# SAS_rev04.net
KiCad netlist of a schematic drawn in EAGLE
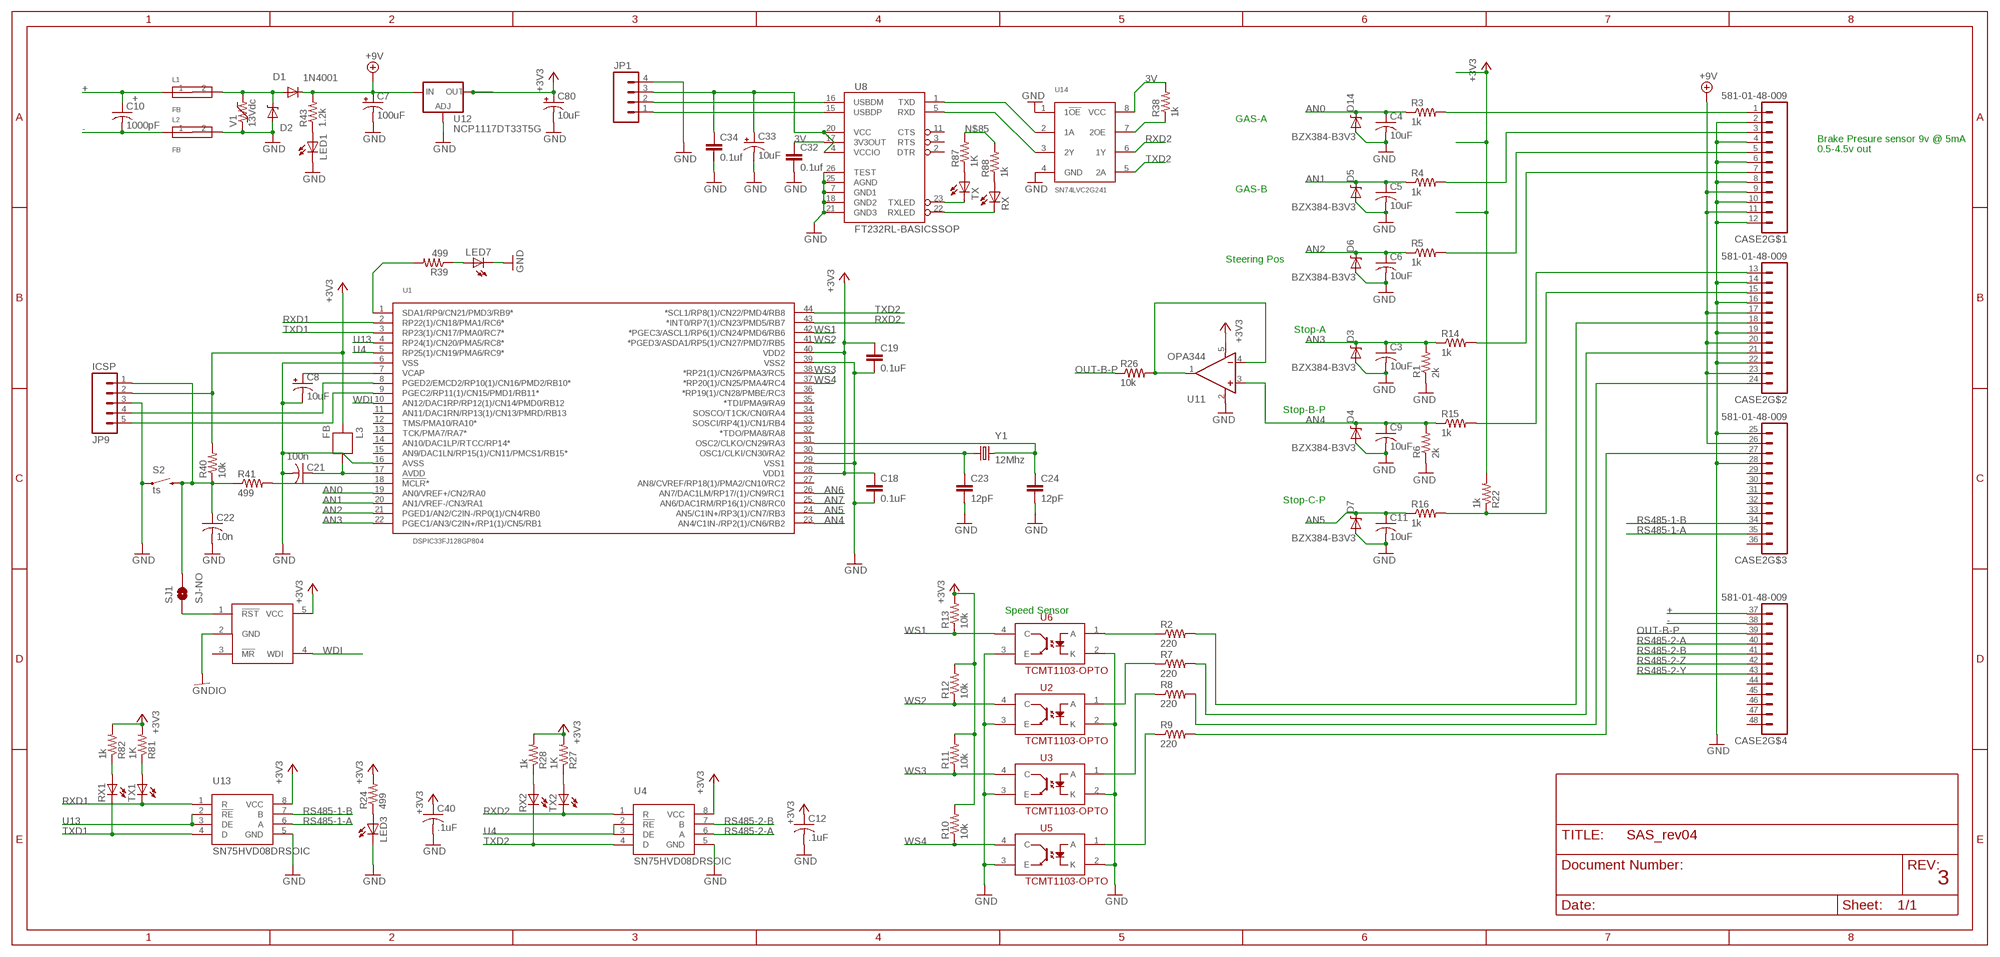
[diagram p0: schematic, sheet 1]

(export (version "E")
  (design (tool "Eeschema 10.0.6"))
  (components
    (comp (ref "C3")
      (value "10uF")
      (footprint "eagle-import:C0805")
      (libsource (lib "eagle-import") (part "C-USC0805"))
    )
    (comp (ref "C4")
      (value "10uF")
      (footprint "eagle-import:C0805")
      (libsource (lib "eagle-import") (part "C-USC0805"))
    )
    (comp (ref "C5")
      (value "10uF")
      (footprint "eagle-import:C0805")
      (libsource (lib "eagle-import") (part "C-USC0805"))
    )
    (comp (ref "C6")
      (value "10uF")
      (footprint "eagle-import:C0805")
      (libsource (lib "eagle-import") (part "C-USC0805"))
    )
    (comp (ref "C7")
      (value "100uF")
      (footprint "eagle-import:EIA7343")
      (libsource (lib "eagle-import") (part "SparkFun-Capacitors_CAP_POL7343"))
    )
    (comp (ref "C8")
      (value "10uF")
      (footprint "eagle-import:EIA3216-16V")
      (fields (field (name "PARTNO") "T491A106M016AT"))
      (libsource (lib "eagle-import") (part "CAP-POL_10UF_16V"))
    )
    (comp (ref "C9")
      (value "10uF")
      (footprint "eagle-import:C0805")
      (libsource (lib "eagle-import") (part "C-USC0805"))
    )
    (comp (ref "C10")
      (value "1000pF")
      (footprint "eagle-import:C1825")
      (libsource (lib "eagle-import") (part "C-USC1825"))
    )
    (comp (ref "C11")
      (value "10uF")
      (footprint "eagle-import:C0805")
      (libsource (lib "eagle-import") (part "C-USC0805"))
    )
    (comp (ref "C12")
      (value ".1uF")
      (footprint "eagle-import:0603")
      (fields (field (name "PARTNO") "CC0603ZRY5V9BB104"))
      (libsource (lib "eagle-import") (part "CAP_0.1UF_50V"))
    )
    (comp (ref "C18")
      (value "0.1uF")
      (footprint "eagle-import:0805")
      (libsource (lib "eagle-import") (part "SparkFun-Capacitors_CAP0805"))
    )
    (comp (ref "C19")
      (value "0.1uF")
      (footprint "eagle-import:0805")
      (libsource (lib "eagle-import") (part "SparkFun-Capacitors_CAP0805"))
    )
    (comp (ref "C21")
      (value "100n")
      (footprint "eagle-import:C0805")
      (libsource (lib "eagle-import") (part "C-USC0805"))
    )
    (comp (ref "C22")
      (value "10n")
      (footprint "eagle-import:0603")
      (fields (field (name "PARTNO") "CL10F103ZB8NNNC"))
      (libsource (lib "eagle-import") (part "CAP_10NF_50V"))
    )
    (comp (ref "C23")
      (value "12pF")
      (footprint "eagle-import:0805")
      (libsource (lib "eagle-import") (part "SparkFun-Capacitors_CAP0805"))
    )
    (comp (ref "C24")
      (value "12pF")
      (footprint "eagle-import:0805")
      (libsource (lib "eagle-import") (part "SparkFun-Capacitors_CAP0805"))
    )
    (comp (ref "C32")
      (value "0.1uf")
      (footprint "eagle-import:0805")
      (libsource (lib "eagle-import") (part "CAP0805"))
    )
    (comp (ref "C33")
      (value "10uF")
      (footprint "eagle-import:EIA3216")
      (libsource (lib "eagle-import") (part "CAP_POL1206"))
    )
    (comp (ref "C34")
      (value "0.1uf")
      (footprint "eagle-import:0805")
      (libsource (lib "eagle-import") (part "CAP0805"))
    )
    (comp (ref "C40")
      (value ".1uF")
      (footprint "eagle-import:0603")
      (fields (field (name "PARTNO") "CC0603ZRY5V9BB104"))
      (libsource (lib "eagle-import") (part "CAP_0.1UF_50V"))
    )
    (comp (ref "C80")
      (value "10uF")
      (footprint "eagle-import:POLC1206")
      (libsource (lib "eagle-import") (part "POLCAP"))
    )
    (comp (ref "CASE2")
      (value "581-01-48-009")
      (footprint "eagle-import:581-01-48-009")
      (libsource (lib "eagle-import") (part "581-01-48-009"))
    )
    (comp (ref "D1")
      (value "1N4001")
      (footprint "eagle-import:SOD123")
      (libsource (lib "eagle-import") (part "DIODE-SOD123"))
    )
    (comp (ref "D2")
      (value "MM5Z30")
      (footprint "eagle-import:SOD-523F")
      (libsource (lib "eagle-import") (part "MM5Z30"))
    )
    (comp (ref "D3")
      (value "BZX384-B3V3")
      (footprint "eagle-import:SOD-323")
      (libsource (lib "eagle-import") (part "DIODE-ZENER-BZT52"))
    )
    (comp (ref "D4")
      (value "BZX384-B3V3")
      (footprint "eagle-import:SOD-323")
      (libsource (lib "eagle-import") (part "DIODE-ZENER-BZT52"))
    )
    (comp (ref "D5")
      (value "BZX384-B3V3")
      (footprint "eagle-import:SOD-323")
      (libsource (lib "eagle-import") (part "DIODE-ZENER-BZT52"))
    )
    (comp (ref "D6")
      (value "BZX384-B3V3")
      (footprint "eagle-import:SOD-323")
      (libsource (lib "eagle-import") (part "DIODE-ZENER-BZT52"))
    )
    (comp (ref "D7")
      (value "BZX384-B3V3")
      (footprint "eagle-import:SOD-323")
      (libsource (lib "eagle-import") (part "DIODE-ZENER-BZT52"))
    )
    (comp (ref "D14")
      (value "BZX384-B3V3")
      (footprint "eagle-import:SOD-323")
      (libsource (lib "eagle-import") (part "DIODE-ZENER-BZT52"))
    )
    (comp (ref "JP1")
      (value "M04POLAR")
      (footprint "eagle-import:MOLEX-1X4")
      (libsource (lib "eagle-import") (part "M04POLAR"))
    )
    (comp (ref "JP9")
      (value "ICSP")
      (footprint "eagle-import:1X05_LOCK_LONGPADS")
      (libsource (lib "eagle-import") (part "M05LOCK_LONGPADS"))
    )
    (comp (ref "L1")
      (value "FB")
      (footprint "eagle-import:0603")
      (libsource (lib "eagle-import") (part "FERITEBEAD"))
    )
    (comp (ref "L2")
      (value "FB")
      (footprint "eagle-import:0603")
      (libsource (lib "eagle-import") (part "FERITEBEAD"))
    )
    (comp (ref "L3")
      (value "FB")
      (footprint "eagle-import:0603")
      (libsource (lib "eagle-import") (part "FB"))
    )
    (comp (ref "LED1")
      (value "LEDCHIP-LED0805")
      (footprint "eagle-import:CHIP-LED0805")
      (libsource (lib "eagle-import") (part "LEDCHIP-LED0805"))
    )
    (comp (ref "LED3")
      (value "LEDCHIP-LED0805")
      (footprint "eagle-import:CHIP-LED0805")
      (libsource (lib "eagle-import") (part "LEDCHIP-LED0805"))
    )
    (comp (ref "LED7")
      (value "LEDCHIP-LED0805")
      (footprint "eagle-import:CHIP-LED0805")
      (libsource (lib "eagle-import") (part "LEDCHIP-LED0805"))
    )
    (comp (ref "R1")
      (value "2k")
      (footprint "eagle-import:0805")
      (fields (field (name "PARTNO") "RC0805FR-072KL"))
      (libsource (lib "eagle-import") (part "FSAE Eletric_RES_2K_1%_0805"))
    )
    (comp (ref "R2")
      (value "220")
      (footprint "eagle-import:0603")
      (fields (field (name "PARTNO") "RC0603FR-07220RL"))
      (libsource (lib "eagle-import") (part "RES_220_1%"))
    )
    (comp (ref "R3")
      (value "1k")
      (footprint "eagle-import:0603")
      (fields (field (name "PARTNO") "RC0603JR-071KL"))
      (libsource (lib "eagle-import") (part "RES_1K_5%"))
    )
    (comp (ref "R4")
      (value "1k")
      (footprint "eagle-import:0603")
      (fields (field (name "PARTNO") "RC0603JR-071KL"))
      (libsource (lib "eagle-import") (part "RES_1K_5%"))
    )
    (comp (ref "R5")
      (value "1k")
      (footprint "eagle-import:0603")
      (fields (field (name "PARTNO") "RC0603JR-071KL"))
      (libsource (lib "eagle-import") (part "RES_1K_5%"))
    )
    (comp (ref "R6")
      (value "2k")
      (footprint "eagle-import:0805")
      (fields (field (name "PARTNO") "RC0805FR-072KL"))
      (libsource (lib "eagle-import") (part "FSAE Eletric_RES_2K_1%_0805"))
    )
    (comp (ref "R7")
      (value "220")
      (footprint "eagle-import:0603")
      (fields (field (name "PARTNO") "RC0603FR-07220RL"))
      (libsource (lib "eagle-import") (part "RES_220_1%"))
    )
    (comp (ref "R8")
      (value "220")
      (footprint "eagle-import:0603")
      (fields (field (name "PARTNO") "RC0603FR-07220RL"))
      (libsource (lib "eagle-import") (part "RES_220_1%"))
    )
    (comp (ref "R9")
      (value "220")
      (footprint "eagle-import:0603")
      (fields (field (name "PARTNO") "RC0603FR-07220RL"))
      (libsource (lib "eagle-import") (part "RES_220_1%"))
    )
    (comp (ref "R10")
      (value "10k")
      (footprint "eagle-import:0603")
      (fields (field (name "PARTNO") "RC0603FR-0710KL"))
      (libsource (lib "eagle-import") (part "RES_10K_1%"))
    )
    (comp (ref "R11")
      (value "10k")
      (footprint "eagle-import:0603")
      (fields (field (name "PARTNO") "RC0603FR-0710KL"))
      (libsource (lib "eagle-import") (part "RES_10K_1%"))
    )
    (comp (ref "R12")
      (value "10k")
      (footprint "eagle-import:0603")
      (fields (field (name "PARTNO") "RC0603FR-0710KL"))
      (libsource (lib "eagle-import") (part "RES_10K_1%"))
    )
    (comp (ref "R13")
      (value "10k")
      (footprint "eagle-import:0603")
      (fields (field (name "PARTNO") "RC0603FR-0710KL"))
      (libsource (lib "eagle-import") (part "RES_10K_1%"))
    )
    (comp (ref "R14")
      (value "1k")
      (footprint "eagle-import:0603")
      (fields (field (name "PARTNO") "RC0603JR-071KL"))
      (libsource (lib "eagle-import") (part "RES_1K_5%"))
    )
    (comp (ref "R15")
      (value "1k")
      (footprint "eagle-import:0603")
      (fields (field (name "PARTNO") "RC0603JR-071KL"))
      (libsource (lib "eagle-import") (part "RES_1K_5%"))
    )
    (comp (ref "R16")
      (value "1k")
      (footprint "eagle-import:0805")
      (fields (field (name "PARTNO") "RC0805FR-071KL"))
      (libsource (lib "eagle-import") (part "FSAE Eletric_RES_1K_1%_0805"))
    )
    (comp (ref "R22")
      (value "1k")
      (footprint "eagle-import:0805")
      (fields (field (name "PARTNO") "RC0805FR-071KL"))
      (libsource (lib "eagle-import") (part "FSAE Eletric_RES_1K_1%_0805"))
    )
    (comp (ref "R24")
      (value "499")
      (footprint "eagle-import:0603")
      (fields (field (name "PARTNO") "RC0603FR-07499RL"))
      (libsource (lib "eagle-import") (part "RES_499_1%"))
    )
    (comp (ref "R26")
      (value "10k")
      (footprint "eagle-import:0805")
      (fields (field (name "PARTNO") "RC0805FR-0710KL"))
      (libsource (lib "eagle-import") (part "FSAE Eletric_RES_10K_1%_0805"))
    )
    (comp (ref "R27")
      (value "1K")
      (footprint "eagle-import:0805")
      (fields (field (name "PARTNO") "RC0805FR-071KL"))
      (libsource (lib "eagle-import") (part "FSAE Eletric_RES_1K_1%_0805"))
    )
    (comp (ref "R28")
      (value "1k")
      (footprint "eagle-import:0805")
      (fields (field (name "PARTNO") "RC0805FR-071KL"))
      (libsource (lib "eagle-import") (part "FSAE Eletric_RES_1K_1%_0805"))
    )
    (comp (ref "R38")
      (value "1k")
      (footprint "eagle-import:0603")
      (fields (field (name "PARTNO") "RC0603JR-071KL"))
      (libsource (lib "eagle-import") (part "RES_1K_5%"))
    )
    (comp (ref "R39")
      (value "499")
      (footprint "eagle-import:0603")
      (fields (field (name "PARTNO") "RC0603FR-07499RL"))
      (libsource (lib "eagle-import") (part "RES_499_1%"))
    )
    (comp (ref "R40")
      (value "10k")
      (footprint "eagle-import:0805")
      (fields (field (name "PARTNO") "RC0805FR-0710KL"))
      (libsource (lib "eagle-import") (part "FSAE Eletric_RES_10K_1%_0805"))
    )
    (comp (ref "R41")
      (value "499")
      (footprint "eagle-import:0805")
      (fields (field (name "PARTNO") "RC0805FR-07499RL"))
      (libsource (lib "eagle-import") (part "FSAE Eletric_RES_499_1%_0805"))
    )
    (comp (ref "R43")
      (value "1.2k")
      (footprint "eagle-import:0805")
      (fields (field (name "PARTNO") "RC0805FR-071K2L"))
      (libsource (lib "eagle-import") (part "RES_1.2K_1%_0805"))
    )
    (comp (ref "R81")
      (value "1K")
      (footprint "eagle-import:0603")
      (fields (field (name "PARTNO") "RC0603JR-071KL"))
      (libsource (lib "eagle-import") (part "RES_1K_5%"))
    )
    (comp (ref "R82")
      (value "1k")
      (footprint "eagle-import:0603")
      (fields (field (name "PARTNO") "RC0603JR-071KL"))
      (libsource (lib "eagle-import") (part "RES_1K_5%"))
    )
    (comp (ref "R87")
      (value "1K")
      (footprint "eagle-import:0603")
      (fields (field (name "PARTNO") "RC0603JR-071KL"))
      (libsource (lib "eagle-import") (part "RES_1K_5%"))
    )
    (comp (ref "R88")
      (value "1k")
      (footprint "eagle-import:0603")
      (fields (field (name "PARTNO") "RC0603JR-071KL"))
      (libsource (lib "eagle-import") (part "RES_1K_5%"))
    )
    (comp (ref "RX")
      (value "LEDCHIPLED_0805")
      (footprint "eagle-import:CHIPLED_0805")
      (libsource (lib "eagle-import") (part "LEDCHIPLED_0805"))
    )
    (comp (ref "RX1")
      (value "LEDCHIPLED_0805")
      (footprint "eagle-import:CHIPLED_0805")
      (libsource (lib "eagle-import") (part "LEDCHIPLED_0805"))
    )
    (comp (ref "RX2")
      (value "LEDCHIPLED_0805")
      (footprint "eagle-import:CHIPLED_0805")
      (libsource (lib "eagle-import") (part "LEDCHIPLED_0805"))
    )
    (comp (ref "S2")
      (value "ts")
      (footprint "eagle-import:TACTILE-PTH")
      (libsource (lib "eagle-import") (part "SWITCH-MOMENTARY-2PTH"))
    )
    (comp (ref "SJ1")
      (value "SJ-NO")
      (footprint "eagle-import:SJ_2S-NO")
      (libsource (lib "eagle-import") (part "SOLDERJUMPERNO"))
    )
    (comp (ref "TX")
      (value "LEDCHIPLED_0805")
      (footprint "eagle-import:CHIPLED_0805")
      (libsource (lib "eagle-import") (part "LEDCHIPLED_0805"))
    )
    (comp (ref "TX1")
      (value "LEDCHIPLED_0805")
      (footprint "eagle-import:CHIPLED_0805")
      (libsource (lib "eagle-import") (part "LEDCHIPLED_0805"))
    )
    (comp (ref "TX2")
      (value "LEDCHIPLED_0805")
      (footprint "eagle-import:CHIPLED_0805")
      (libsource (lib "eagle-import") (part "LEDCHIPLED_0805"))
    )
    (comp (ref "U1")
      (value "DSPIC33FJ128GP804")
      (footprint "eagle-import:TQFP-44")
      (fields (field (name "PARTNO") "DSPIC33FJ128GP804-I/PT"))
      (libsource (lib "eagle-import") (part "DSPIC33FJ128GP804"))
    )
    (comp (ref "U2")
      (value "TCMT1103-OPTO")
      (footprint "eagle-import:SSOP-4")
      (libsource (lib "eagle-import") (part "TCMT1103-OPTO"))
    )
    (comp (ref "U3")
      (value "TCMT1103-OPTO")
      (footprint "eagle-import:SSOP-4")
      (libsource (lib "eagle-import") (part "TCMT1103-OPTO"))
    )
    (comp (ref "U4")
      (value "SN75HVD08DRSOIC")
      (footprint "eagle-import:SO-8")
      (fields (field (name "PARTNO") "SN75176BDR"))
      (libsource (lib "eagle-import") (part "SN75HVD08DRSOIC"))
    )
    (comp (ref "U5")
      (value "TCMT1103-OPTO")
      (footprint "eagle-import:SSOP-4")
      (libsource (lib "eagle-import") (part "TCMT1103-OPTO"))
    )
    (comp (ref "U6")
      (value "TCMT1103-OPTO")
      (footprint "eagle-import:SSOP-4")
      (libsource (lib "eagle-import") (part "TCMT1103-OPTO"))
    )
    (comp (ref "U8")
      (value "FT232RL-BASICSSOP")
      (footprint "eagle-import:SSOP28DB")
      (libsource (lib "eagle-import") (part "FT232RL-BASICSSOP"))
    )
    (comp (ref "U9")
      (value "MAX823")
      (footprint "eagle-import:SOT23-5L")
      (libsource (lib "eagle-import") (part "MAX823"))
    )
    (comp (ref "U11")
      (value "OPA344")
      (footprint "eagle-import:SOT23-5")
      (libsource (lib "eagle-import") (part "OPA344"))
    )
    (comp (ref "U12")
      (value "NCP1117DT33T5G")
      (footprint "eagle-import:V-REG_DPACK")
      (libsource (lib "eagle-import") (part "V_REG_317DPACK"))
    )
    (comp (ref "U13")
      (value "SN75HVD08DRSOIC")
      (footprint "eagle-import:SO-8")
      (fields (field (name "PARTNO") "SN75176BDR"))
      (libsource (lib "eagle-import") (part "SN75HVD08DRSOIC"))
    )
    (comp (ref "U14")
      (value "SN74LVC2G241")
      (footprint "eagle-import:VFSOP-8")
      (fields (field (name "PARTNO") "SN74LVC2G241DCUR"))
      (libsource (lib "eagle-import") (part "SN74LVC2G241"))
    )
    (comp (ref "V1")
      (value "13Vdc")
      (footprint "eagle-import:0603")
      (libsource (lib "eagle-import") (part "VAR-RES"))
    )
    (comp (ref "Y1")
      (value "12Mhz")
      (footprint "eagle-import:CRYSTAL-SMD-5X3")
      (libsource (lib "eagle-import") (part "CRYSTAL5X3"))
    )
  )
  (nets
    (net (code "1") (name "+3V3") (class "Default")
      (node (ref "C12") (pin "1") (pinfunction "+_1") (pintype "passive"))
      (node (ref "C18") (pin "1") (pinfunction "1_1") (pintype "passive"))
      (node (ref "C19") (pin "1") (pinfunction "1_1") (pintype "passive"))
      (node (ref "C40") (pin "1") (pinfunction "+_1") (pintype "passive"))
      (node (ref "C80") (pin "1") (pinfunction "+_1") (pintype "passive"))
      (node (ref "JP9") (pin "2") (pinfunction "2_2") (pintype "passive"))
      (node (ref "L3") (pin "2") (pinfunction "P$2_2") (pintype "bidirectional"))
      (node (ref "R10") (pin "2") (pinfunction "2_2") (pintype "passive"))
      (node (ref "R11") (pin "2") (pinfunction "2_2") (pintype "passive"))
      (node (ref "R12") (pin "2") (pinfunction "2_2") (pintype "passive"))
      (node (ref "R13") (pin "2") (pinfunction "2_2") (pintype "passive"))
      (node (ref "R22") (pin "2") (pinfunction "2_2") (pintype "passive"))
      (node (ref "R24") (pin "2") (pinfunction "2_2") (pintype "passive"))
      (node (ref "R27") (pin "2") (pinfunction "2_2") (pintype "passive"))
      (node (ref "R28") (pin "2") (pinfunction "2_2") (pintype "passive"))
      (node (ref "R40") (pin "2") (pinfunction "2_2") (pintype "passive"))
      (node (ref "R81") (pin "2") (pinfunction "2_2") (pintype "passive"))
      (node (ref "R82") (pin "2") (pinfunction "2_2") (pintype "passive"))
      (node (ref "U1") (pin "28") (pinfunction "VDD1_28") (pintype "bidirectional"))
      (node (ref "U1") (pin "40") (pinfunction "VDD2_40") (pintype "bidirectional"))
      (node (ref "U11") (pin "5") (pinfunction "V+_5") (pintype "power_in"))
      (node (ref "U12") (pin "4") (pinfunction "OUT_4") (pintype "output"))
      (node (ref "U13") (pin "8") (pinfunction "VCC_8") (pintype "bidirectional"))
      (node (ref "U4") (pin "8") (pinfunction "VCC_8") (pintype "bidirectional"))
      (node (ref "U9") (pin "5") (pinfunction "VCC_5") (pintype "bidirectional"))
    )
    (net (code "2") (name "+9V") (class "Default")
      (node (ref "C7") (pin "A") (pinfunction "+_A") (pintype "passive"))
      (node (ref "CASE2") (pin "11") (pinfunction "11_11") (pintype "passive"))
      (node (ref "CASE2") (pin "17") (pinfunction "5_17") (pintype "passive"))
      (node (ref "CASE2") (pin "20") (pinfunction "8_20") (pintype "passive"))
      (node (ref "CASE2") (pin "23") (pinfunction "11_23") (pintype "passive"))
      (node (ref "CASE2") (pin "26") (pinfunction "2_26") (pintype "passive"))
      (node (ref "CASE2") (pin "9") (pinfunction "9_9") (pintype "passive"))
      (node (ref "D1") (pin "C") (pinfunction "C_C") (pintype "passive"))
      (node (ref "R43") (pin "2") (pinfunction "2_2") (pintype "passive"))
      (node (ref "U12") (pin "3") (pinfunction "IN_3") (pintype "input"))
    )
    (net (code "3") (name "/+") (class "Default")
      (node (ref "C10") (pin "1") (pinfunction "1_1") (pintype "passive"))
      (node (ref "CASE2") (pin "37") (pinfunction "1_37") (pintype "passive"))
      (node (ref "L1") (pin "1") (pinfunction "P$1_1") (pintype "bidirectional"))
    )
    (net (code "4") (name "/-") (class "Default")
      (node (ref "C10") (pin "2") (pinfunction "2_2") (pintype "passive"))
      (node (ref "CASE2") (pin "38") (pinfunction "2_38") (pintype "passive"))
      (node (ref "L2") (pin "1") (pinfunction "P$1_1") (pintype "bidirectional"))
    )
    (net (code "5") (name "/3V") (class "Default")
      (node (ref "C32") (pin "1") (pinfunction "1_1") (pintype "passive"))
      (node (ref "R38") (pin "2") (pinfunction "2_2") (pintype "passive"))
      (node (ref "U14") (pin "8") (pinfunction "VCC_8") (pintype "bidirectional"))
      (node (ref "U8") (pin "17") (pinfunction "3V3OUT_17") (pintype "output"))
    )
    (net (code "6") (name "/AN0") (class "Default")
      (node (ref "C4") (pin "1") (pinfunction "1_1") (pintype "passive"))
      (node (ref "D14") (pin "1") (pinfunction "C_1") (pintype "passive"))
      (node (ref "R3") (pin "1") (pinfunction "1_1") (pintype "passive"))
      (node (ref "U1") (pin "19") (pinfunction "AN0/VREF+/CN2/RA0_19") (pintype "bidirectional"))
    )
    (net (code "7") (name "/AN1") (class "Default")
      (node (ref "C5") (pin "1") (pinfunction "1_1") (pintype "passive"))
      (node (ref "D5") (pin "1") (pinfunction "C_1") (pintype "passive"))
      (node (ref "R4") (pin "1") (pinfunction "1_1") (pintype "passive"))
      (node (ref "U1") (pin "20") (pinfunction "AN1/VREF-/CN3/RA1_20") (pintype "bidirectional"))
    )
    (net (code "8") (name "/AN2") (class "Default")
      (node (ref "C6") (pin "1") (pinfunction "1_1") (pintype "passive"))
      (node (ref "D6") (pin "1") (pinfunction "C_1") (pintype "passive"))
      (node (ref "R5") (pin "1") (pinfunction "1_1") (pintype "passive"))
      (node (ref "U1") (pin "21") (pinfunction "PGED1/AN2/C2IN-/RP0(1)/CN4/RB0_21") (pintype "bidirectional"))
    )
    (net (code "9") (name "/AN3") (class "Default")
      (node (ref "C3") (pin "1") (pinfunction "1_1") (pintype "passive"))
      (node (ref "D3") (pin "1") (pinfunction "C_1") (pintype "passive"))
      (node (ref "R1") (pin "2") (pinfunction "2_2") (pintype "passive"))
      (node (ref "R14") (pin "1") (pinfunction "1_1") (pintype "passive"))
      (node (ref "U1") (pin "22") (pinfunction "PGEC1/AN3/C2IN+/RP1(1)/CN5/RB1_22") (pintype "bidirectional"))
    )
    (net (code "10") (name "/AN4") (class "Default")
      (node (ref "C9") (pin "1") (pinfunction "1_1") (pintype "passive"))
      (node (ref "D4") (pin "1") (pinfunction "C_1") (pintype "passive"))
      (node (ref "R15") (pin "1") (pinfunction "1_1") (pintype "passive"))
      (node (ref "R6") (pin "2") (pinfunction "2_2") (pintype "passive"))
      (node (ref "U1") (pin "23") (pinfunction "AN4/C1IN-/RP2(1)/CN6/RB2_23") (pintype "bidirectional"))
      (node (ref "U11") (pin "3") (pinfunction "+IN_3") (pintype "input"))
    )
    (net (code "11") (name "/AN5") (class "Default")
      (node (ref "C11") (pin "1") (pinfunction "1_1") (pintype "passive"))
      (node (ref "D7") (pin "1") (pinfunction "C_1") (pintype "passive"))
      (node (ref "R16") (pin "1") (pinfunction "1_1") (pintype "passive"))
      (node (ref "U1") (pin "24") (pinfunction "AN5/C1IN+/RP3(1)/CN7/RB3_24") (pintype "bidirectional"))
    )
    (net (code "12") (name "/AN6") (class "Default")
      (node (ref "U1") (pin "26") (pinfunction "AN7/DAC1LM/RP17/(1)/CN9/RC1_26") (pintype "bidirectional"))
    )
    (net (code "13") (name "/AN7") (class "Default")
      (node (ref "U1") (pin "25") (pinfunction "AN6/DAC1RM/RP16(1)/CN8/RC0_25") (pintype "bidirectional"))
    )
    (net (code "14") (name "/N$85") (class "Default")
      (node (ref "C33") (pin "A") (pinfunction "+_A") (pintype "passive"))
      (node (ref "C34") (pin "1") (pinfunction "1_1") (pintype "passive"))
      (node (ref "JP1") (pin "3") (pinfunction "3_3") (pintype "passive"))
      (node (ref "R87") (pin "2") (pinfunction "2_2") (pintype "passive"))
      (node (ref "R88") (pin "2") (pinfunction "2_2") (pintype "passive"))
      (node (ref "U8") (pin "20") (pinfunction "VCC_20") (pintype "power_in"))
      (node (ref "U8") (pin "4") (pinfunction "VCCIO_4") (pintype "power_in"))
    )
    (net (code "15") (name "/OUT-B-P") (class "Default")
      (node (ref "CASE2") (pin "39") (pinfunction "3_39") (pintype "passive"))
      (node (ref "R26") (pin "1") (pinfunction "1_1") (pintype "passive"))
    )
    (net (code "16") (name "/RS485-1-A") (class "Default")
      (node (ref "CASE2") (pin "35") (pinfunction "11_35") (pintype "passive"))
      (node (ref "U13") (pin "6") (pinfunction "A_6") (pintype "bidirectional"))
    )
    (net (code "17") (name "/RS485-1-B") (class "Default")
      (node (ref "CASE2") (pin "34") (pinfunction "10_34") (pintype "passive"))
      (node (ref "U13") (pin "7") (pinfunction "B_7") (pintype "bidirectional"))
    )
    (net (code "18") (name "/RS485-2-A") (class "Default")
      (node (ref "CASE2") (pin "40") (pinfunction "4_40") (pintype "passive"))
      (node (ref "U4") (pin "6") (pinfunction "A_6") (pintype "bidirectional"))
    )
    (net (code "19") (name "/RS485-2-B") (class "Default")
      (node (ref "CASE2") (pin "41") (pinfunction "5_41") (pintype "passive"))
      (node (ref "U4") (pin "7") (pinfunction "B_7") (pintype "bidirectional"))
    )
    (net (code "20") (name "/RS485-2-Y") (class "Default")
      (node (ref "CASE2") (pin "43") (pinfunction "7_43") (pintype "passive"))
    )
    (net (code "21") (name "/RS485-2-Z") (class "Default")
      (node (ref "CASE2") (pin "42") (pinfunction "6_42") (pintype "passive"))
    )
    (net (code "22") (name "/RXD1") (class "Default")
      (node (ref "TX1") (pin "C") (pinfunction "C_C") (pintype "passive"))
      (node (ref "U1") (pin "2") (pinfunction "RP22(1)/CN18/PMA1/RC6*_2") (pintype "bidirectional"))
      (node (ref "U13") (pin "1") (pinfunction "R_1") (pintype "bidirectional"))
    )
    (net (code "23") (name "/RXD2") (class "Default")
      (node (ref "TX2") (pin "C") (pinfunction "C_C") (pintype "passive"))
      (node (ref "U1") (pin "43") (pinfunction "*INT0/RP7(1)/CN23/PMD5/RB7_43") (pintype "bidirectional"))
      (node (ref "U14") (pin "6") (pinfunction "1Y_6") (pintype "bidirectional"))
      (node (ref "U4") (pin "1") (pinfunction "R_1") (pintype "bidirectional"))
    )
    (net (code "24") (name "/TXD1") (class "Default")
      (node (ref "RX1") (pin "C") (pinfunction "C_C") (pintype "passive"))
      (node (ref "U1") (pin "3") (pinfunction "RP23(1)/CN17/PMA0/RC7*_3") (pintype "bidirectional"))
      (node (ref "U13") (pin "4") (pinfunction "D_4") (pintype "bidirectional"))
    )
    (net (code "25") (name "/TXD2") (class "Default")
      (node (ref "RX2") (pin "C") (pinfunction "C_C") (pintype "passive"))
      (node (ref "U1") (pin "44") (pinfunction "*SCL1/RP8(1)/CN22/PMD4/RB8_44") (pintype "bidirectional"))
      (node (ref "U14") (pin "5") (pinfunction "2A_5") (pintype "bidirectional"))
      (node (ref "U4") (pin "4") (pinfunction "D_4") (pintype "bidirectional"))
    )
    (net (code "26") (name "/U4") (class "Default")
      (node (ref "U1") (pin "5") (pinfunction "RP25(1)/CN19/PMA6/RC9*_5") (pintype "bidirectional"))
      (node (ref "U4") (pin "2") (pinfunction "~{RE}_2") (pintype "bidirectional"))
      (node (ref "U4") (pin "3") (pinfunction "DE_3") (pintype "bidirectional"))
    )
    (net (code "27") (name "/U13") (class "Default")
      (node (ref "U1") (pin "4") (pinfunction "RP24(1)/CN20/PMA5/RC8*_4") (pintype "bidirectional"))
      (node (ref "U13") (pin "2") (pinfunction "~{RE}_2") (pintype "bidirectional"))
      (node (ref "U13") (pin "3") (pinfunction "DE_3") (pintype "bidirectional"))
    )
    (net (code "28") (name "/WDI") (class "Default")
      (node (ref "U1") (pin "10") (pinfunction "AN12/DAC1RP/RP12(1)/CN14/PMD0/RB12_10") (pintype "bidirectional"))
      (node (ref "U9") (pin "4") (pinfunction "WDI_4") (pintype "bidirectional"))
    )
    (net (code "29") (name "/WS1") (class "Default")
      (node (ref "R13") (pin "1") (pinfunction "1_1") (pintype "passive"))
      (node (ref "U1") (pin "42") (pinfunction "*PGEC3/ASCL1/RP6(1)/CN24/PMD6/RB6_42") (pintype "bidirectional"))
      (node (ref "U6") (pin "4") (pinfunction "C_4") (pintype "bidirectional"))
    )
    (net (code "30") (name "/WS2") (class "Default")
      (node (ref "R12") (pin "1") (pinfunction "1_1") (pintype "passive"))
      (node (ref "U1") (pin "41") (pinfunction "*PGED3/ASDA1/RP5(1)/CN27/PMD7/RB5_41") (pintype "bidirectional"))
      (node (ref "U2") (pin "4") (pinfunction "C_4") (pintype "bidirectional"))
    )
    (net (code "31") (name "/WS3") (class "Default")
      (node (ref "R11") (pin "1") (pinfunction "1_1") (pintype "passive"))
      (node (ref "U1") (pin "38") (pinfunction "*RP21(1)/CN26/PMA3/RC5_38") (pintype "bidirectional"))
      (node (ref "U3") (pin "4") (pinfunction "C_4") (pintype "bidirectional"))
    )
    (net (code "32") (name "/WS4") (class "Default")
      (node (ref "R10") (pin "1") (pinfunction "1_1") (pintype "passive"))
      (node (ref "U1") (pin "37") (pinfunction "*RP20(1)/CN25/PMA4/RC4_37") (pintype "bidirectional"))
      (node (ref "U5") (pin "4") (pinfunction "C_4") (pintype "bidirectional"))
    )
    (net (code "33") (name "GND") (class "Default")
      (node (ref "C11") (pin "2") (pinfunction "2_2") (pintype "passive"))
      (node (ref "C12") (pin "2") (pinfunction "-_2") (pintype "passive"))
      (node (ref "C18") (pin "2") (pinfunction "2_2") (pintype "passive"))
      (node (ref "C19") (pin "2") (pinfunction "2_2") (pintype "passive"))
      (node (ref "C21") (pin "2") (pinfunction "2_2") (pintype "passive"))
      (node (ref "C22") (pin "2") (pinfunction "-_2") (pintype "passive"))
      (node (ref "C23") (pin "2") (pinfunction "2_2") (pintype "passive"))
      (node (ref "C24") (pin "2") (pinfunction "2_2") (pintype "passive"))
      (node (ref "C3") (pin "2") (pinfunction "2_2") (pintype "passive"))
      (node (ref "C32") (pin "2") (pinfunction "2_2") (pintype "passive"))
      (node (ref "C33") (pin "C") (pinfunction "-_C") (pintype "passive"))
      (node (ref "C34") (pin "2") (pinfunction "2_2") (pintype "passive"))
      (node (ref "C4") (pin "2") (pinfunction "2_2") (pintype "passive"))
      (node (ref "C40") (pin "2") (pinfunction "-_2") (pintype "passive"))
      (node (ref "C5") (pin "2") (pinfunction "2_2") (pintype "passive"))
      (node (ref "C6") (pin "2") (pinfunction "2_2") (pintype "passive"))
      (node (ref "C7") (pin "C") (pinfunction "-_C") (pintype "passive"))
      (node (ref "C8") (pin "C") (pinfunction "-_C") (pintype "passive"))
      (node (ref "C80") (pin "2") (pinfunction "-_2") (pintype "passive"))
      (node (ref "C9") (pin "2") (pinfunction "2_2") (pintype "passive"))
      (node (ref "CASE2") (pin "10") (pinfunction "10_10") (pintype "passive"))
      (node (ref "CASE2") (pin "12") (pinfunction "12_12") (pintype "passive"))
      (node (ref "CASE2") (pin "14") (pinfunction "2_14") (pintype "passive"))
      (node (ref "CASE2") (pin "16") (pinfunction "4_16") (pintype "passive"))
      (node (ref "CASE2") (pin "19") (pinfunction "7_19") (pintype "passive"))
      (node (ref "CASE2") (pin "2") (pinfunction "2_2") (pintype "passive"))
      (node (ref "CASE2") (pin "22") (pinfunction "10_22") (pintype "passive"))
      (node (ref "CASE2") (pin "25") (pinfunction "1_25") (pintype "passive"))
      (node (ref "CASE2") (pin "28") (pinfunction "4_28") (pintype "passive"))
      (node (ref "CASE2") (pin "4") (pinfunction "4_4") (pintype "passive"))
      (node (ref "CASE2") (pin "6") (pinfunction "6_6") (pintype "passive"))
      (node (ref "CASE2") (pin "8") (pinfunction "8_8") (pintype "passive"))
      (node (ref "D14") (pin "2") (pinfunction "A_2") (pintype "passive"))
      (node (ref "D2") (pin "A") (pinfunction "A_A") (pintype "passive"))
      (node (ref "D3") (pin "2") (pinfunction "A_2") (pintype "passive"))
      (node (ref "D4") (pin "2") (pinfunction "A_2") (pintype "passive"))
      (node (ref "D5") (pin "2") (pinfunction "A_2") (pintype "passive"))
      (node (ref "D6") (pin "2") (pinfunction "A_2") (pintype "passive"))
      (node (ref "D7") (pin "2") (pinfunction "A_2") (pintype "passive"))
      (node (ref "JP1") (pin "4") (pinfunction "4_4") (pintype "passive"))
      (node (ref "JP9") (pin "3") (pinfunction "3_3") (pintype "passive"))
      (node (ref "L2") (pin "2") (pinfunction "P$2_2") (pintype "bidirectional"))
      (node (ref "LED1") (pin "C") (pinfunction "C_C") (pintype "passive"))
      (node (ref "LED3") (pin "C") (pinfunction "C_C") (pintype "passive"))
      (node (ref "LED7") (pin "C") (pinfunction "C_C") (pintype "passive"))
      (node (ref "R1") (pin "1") (pinfunction "1_1") (pintype "passive"))
      (node (ref "R6") (pin "1") (pinfunction "1_1") (pintype "passive"))
      (node (ref "S2") (pin "1") (pinfunction "1_1") (pintype "passive"))
      (node (ref "U1") (pin "16") (pinfunction "AVSS_16") (pintype "bidirectional"))
      (node (ref "U1") (pin "29") (pinfunction "VSS1_29") (pintype "bidirectional"))
      (node (ref "U1") (pin "39") (pinfunction "VSS2_39") (pintype "bidirectional"))
      (node (ref "U1") (pin "6") (pinfunction "VSS_6") (pintype "bidirectional"))
      (node (ref "U11") (pin "2") (pinfunction "V-_2") (pintype "power_in"))
      (node (ref "U12") (pin "1") (pinfunction "ADJ_1") (pintype "input"))
      (node (ref "U13") (pin "5") (pinfunction "GND_5") (pintype "bidirectional"))
      (node (ref "U14") (pin "1") (pinfunction "1~{OE}_1") (pintype "bidirectional"))
      (node (ref "U14") (pin "4") (pinfunction "GND_4") (pintype "bidirectional"))
      (node (ref "U2") (pin "2") (pinfunction "K_2") (pintype "bidirectional"))
      (node (ref "U2") (pin "3") (pinfunction "E_3") (pintype "bidirectional"))
      (node (ref "U3") (pin "2") (pinfunction "K_2") (pintype "bidirectional"))
      (node (ref "U3") (pin "3") (pinfunction "E_3") (pintype "bidirectional"))
      (node (ref "U4") (pin "5") (pinfunction "GND_5") (pintype "bidirectional"))
      (node (ref "U5") (pin "2") (pinfunction "K_2") (pintype "bidirectional"))
      (node (ref "U5") (pin "3") (pinfunction "E_3") (pintype "bidirectional"))
      (node (ref "U6") (pin "2") (pinfunction "K_2") (pintype "bidirectional"))
      (node (ref "U6") (pin "3") (pinfunction "E_3") (pintype "bidirectional"))
      (node (ref "U8") (pin "18") (pinfunction "GND2_18") (pintype "power_in"))
      (node (ref "U8") (pin "21") (pinfunction "GND3_21") (pintype "power_in"))
      (node (ref "U8") (pin "25") (pinfunction "AGND_25") (pintype "power_in"))
      (node (ref "U8") (pin "26") (pinfunction "TEST_26") (pintype "input"))
      (node (ref "U8") (pin "7") (pinfunction "GND1_7") (pintype "power_in"))
      (node (ref "V1") (pin "1") (pinfunction "1_1") (pintype "passive"))
    )
    (net (code "34") (name "GNDIO") (class "Default")
      (node (ref "U9") (pin "2") (pinfunction "GND_2") (pintype "bidirectional"))
    )
    (net (code "35") (name "Net-(C8-+)") (class "Default")
      (node (ref "C8") (pin "A") (pinfunction "+_A") (pintype "passive"))
      (node (ref "U1") (pin "7") (pinfunction "VCAP_7") (pintype "bidirectional"))
    )
    (net (code "36") (name "Net-(C22-+)") (class "Default")
      (node (ref "C22") (pin "1") (pinfunction "+_1") (pintype "passive"))
      (node (ref "JP9") (pin "1") (pinfunction "1_1") (pintype "passive"))
      (node (ref "R40") (pin "1") (pinfunction "1_1") (pintype "passive"))
      (node (ref "R41") (pin "1") (pinfunction "1_1") (pintype "passive"))
      (node (ref "S2") (pin "3") (pinfunction "2_3") (pintype "passive"))
      (node (ref "SJ1") (pin "2") (pinfunction "2_2") (pintype "passive"))
    )
    (net (code "37") (name "Net-(CASE2-Pad1)") (class "Default")
      (node (ref "CASE2") (pin "1") (pinfunction "1_1") (pintype "passive"))
      (node (ref "R3") (pin "2") (pinfunction "2_2") (pintype "passive"))
    )
    (net (code "38") (name "Net-(CASE2-Pad3)") (class "Default")
      (node (ref "CASE2") (pin "3") (pinfunction "3_3") (pintype "passive"))
      (node (ref "R4") (pin "2") (pinfunction "2_2") (pintype "passive"))
    )
    (net (code "39") (name "Net-(CASE2-Pad5)") (class "Default")
      (node (ref "CASE2") (pin "5") (pinfunction "5_5") (pintype "passive"))
      (node (ref "R5") (pin "2") (pinfunction "2_2") (pintype "passive"))
    )
    (net (code "40") (name "Net-(CASE2-Pad7)") (class "Default")
      (node (ref "CASE2") (pin "7") (pinfunction "7_7") (pintype "passive"))
      (node (ref "R14") (pin "2") (pinfunction "2_2") (pintype "passive"))
    )
    (net (code "41") (name "Net-(CASE2B-1)") (class "Default")
      (node (ref "CASE2") (pin "13") (pinfunction "1_13") (pintype "passive"))
      (node (ref "R15") (pin "2") (pinfunction "2_2") (pintype "passive"))
    )
    (net (code "42") (name "Net-(CASE2B-3)") (class "Default")
      (node (ref "CASE2") (pin "15") (pinfunction "3_15") (pintype "passive"))
      (node (ref "R16") (pin "2") (pinfunction "2_2") (pintype "passive"))
      (node (ref "R22") (pin "1") (pinfunction "1_1") (pintype "passive"))
    )
    (net (code "43") (name "Net-(CASE2B-6)") (class "Default")
      (node (ref "CASE2") (pin "18") (pinfunction "6_18") (pintype "passive"))
      (node (ref "R2") (pin "2") (pinfunction "2_2") (pintype "passive"))
    )
    (net (code "44") (name "Net-(CASE2B-9)") (class "Default")
      (node (ref "CASE2") (pin "21") (pinfunction "9_21") (pintype "passive"))
      (node (ref "R7") (pin "2") (pinfunction "2_2") (pintype "passive"))
    )
    (net (code "45") (name "Net-(CASE2B-12)") (class "Default")
      (node (ref "CASE2") (pin "24") (pinfunction "12_24") (pintype "passive"))
      (node (ref "R8") (pin "2") (pinfunction "2_2") (pintype "passive"))
    )
    (net (code "46") (name "Net-(CASE2C-3)") (class "Default")
      (node (ref "CASE2") (pin "27") (pinfunction "3_27") (pintype "passive"))
      (node (ref "R9") (pin "2") (pinfunction "2_2") (pintype "passive"))
    )
    (net (code "47") (name "Net-(L1-P$2)") (class "Default")
      (node (ref "D1") (pin "A") (pinfunction "A_A") (pintype "passive"))
      (node (ref "D2") (pin "C") (pinfunction "C_C") (pintype "passive"))
      (node (ref "L1") (pin "2") (pinfunction "P$2_2") (pintype "bidirectional"))
      (node (ref "V1") (pin "2") (pinfunction "2_2") (pintype "passive"))
    )
    (net (code "48") (name "Net-(L3-P$1)") (class "Default")
      (node (ref "C21") (pin "1") (pinfunction "1_1") (pintype "passive"))
      (node (ref "L3") (pin "1") (pinfunction "P$1_1") (pintype "bidirectional"))
      (node (ref "U1") (pin "17") (pinfunction "AVDD_17") (pintype "bidirectional"))
    )
    (net (code "49") (name "Net-(LED1-PadA)") (class "Default")
      (node (ref "LED1") (pin "A") (pinfunction "A_A") (pintype "passive"))
      (node (ref "R43") (pin "1") (pinfunction "1_1") (pintype "passive"))
    )
    (net (code "50") (name "Net-(LED3-PadA)") (class "Default")
      (node (ref "LED3") (pin "A") (pinfunction "A_A") (pintype "passive"))
      (node (ref "R24") (pin "1") (pinfunction "1_1") (pintype "passive"))
    )
    (net (code "51") (name "Net-(LED7-PadA)") (class "Default")
      (node (ref "LED7") (pin "A") (pinfunction "A_A") (pintype "passive"))
      (node (ref "R39") (pin "1") (pinfunction "1_1") (pintype "passive"))
    )
    (net (code "52") (name "Net-(R27-Pad1)") (class "Default")
      (node (ref "R27") (pin "1") (pinfunction "1_1") (pintype "passive"))
      (node (ref "TX2") (pin "A") (pinfunction "A_A") (pintype "passive"))
    )
    (net (code "53") (name "Net-(R28-Pad1)") (class "Default")
      (node (ref "R28") (pin "1") (pinfunction "1_1") (pintype "passive"))
      (node (ref "RX2") (pin "A") (pinfunction "A_A") (pintype "passive"))
    )
    (net (code "54") (name "Net-(R81-Pad1)") (class "Default")
      (node (ref "R81") (pin "1") (pinfunction "1_1") (pintype "passive"))
      (node (ref "TX1") (pin "A") (pinfunction "A_A") (pintype "passive"))
    )
    (net (code "55") (name "Net-(R82-Pad1)") (class "Default")
      (node (ref "R82") (pin "1") (pinfunction "1_1") (pintype "passive"))
      (node (ref "RX1") (pin "A") (pinfunction "A_A") (pintype "passive"))
    )
    (net (code "56") (name "Net-(R87-Pad1)") (class "Default")
      (node (ref "R87") (pin "1") (pinfunction "1_1") (pintype "passive"))
      (node (ref "TX") (pin "A") (pinfunction "A_A") (pintype "passive"))
    )
    (net (code "57") (name "Net-(R88-Pad1)") (class "Default")
      (node (ref "R88") (pin "1") (pinfunction "1_1") (pintype "passive"))
      (node (ref "RX") (pin "A") (pinfunction "A_A") (pintype "passive"))
    )
    (net (code "58") (name "Net-(U1-OSC1{slash}CLKI{slash}CN30{slash}RA2)") (class "Default")
      (node (ref "C23") (pin "1") (pinfunction "1_1") (pintype "passive"))
      (node (ref "U1") (pin "30") (pinfunction "OSC1/CLKI/CN30/RA2_30") (pintype "bidirectional"))
      (node (ref "Y1") (pin "1") (pinfunction "1_1") (pintype "passive"))
    )
    (net (code "59") (name "Net-(U1-OSC2{slash}CLKO{slash}CN29{slash}RA3)") (class "Default")
      (node (ref "C24") (pin "1") (pinfunction "1_1") (pintype "passive"))
      (node (ref "U1") (pin "31") (pinfunction "OSC2/CLKO/CN29/RA3_31") (pintype "bidirectional"))
      (node (ref "Y1") (pin "3") (pinfunction "2_3") (pintype "passive"))
    )
    (net (code "60") (name "Net-(U1-PGEC2{slash}RP11(1){slash}CN15{slash}PMD1{slash}RB11*)") (class "Default")
      (node (ref "JP9") (pin "5") (pinfunction "5_5") (pintype "passive"))
      (node (ref "U1") (pin "9") (pinfunction "PGEC2/RP11(1)/CN15/PMD1/RB11*_9") (pintype "bidirectional"))
    )
    (net (code "61") (name "Net-(U1-PGED2{slash}EMCD2{slash}RP10(1){slash}CN16{slash}PMD2{slash}RB10*)") (class "Default")
      (node (ref "JP9") (pin "4") (pinfunction "4_4") (pintype "passive"))
      (node (ref "U1") (pin "8") (pinfunction "PGED2/EMCD2/RP10(1)/CN16/PMD2/RB10*_8") (pintype "bidirectional"))
    )
    (net (code "62") (name "Net-(U1-SDA1{slash}RP9{slash}CN21{slash}PMD3{slash}RB9*)") (class "Default")
      (node (ref "R39") (pin "2") (pinfunction "2_2") (pintype "passive"))
      (node (ref "U1") (pin "1") (pinfunction "SDA1/RP9/CN21/PMD3/RB9*_1") (pintype "bidirectional"))
    )
    (net (code "63") (name "Net-(U1-~{MCLR}*)") (class "Default")
      (node (ref "R41") (pin "2") (pinfunction "2_2") (pintype "passive"))
      (node (ref "U1") (pin "18") (pinfunction "~{MCLR}*_18") (pintype "bidirectional"))
    )
    (net (code "64") (name "Net-(U2-A)") (class "Default")
      (node (ref "R7") (pin "1") (pinfunction "1_1") (pintype "passive"))
      (node (ref "U2") (pin "1") (pinfunction "A_1") (pintype "bidirectional"))
    )
    (net (code "65") (name "Net-(U3-A)") (class "Default")
      (node (ref "R8") (pin "1") (pinfunction "1_1") (pintype "passive"))
      (node (ref "U3") (pin "1") (pinfunction "A_1") (pintype "bidirectional"))
    )
    (net (code "66") (name "Net-(U5-A)") (class "Default")
      (node (ref "R9") (pin "1") (pinfunction "1_1") (pintype "passive"))
      (node (ref "U5") (pin "1") (pinfunction "A_1") (pintype "bidirectional"))
    )
    (net (code "67") (name "Net-(U6-A)") (class "Default")
      (node (ref "R2") (pin "1") (pinfunction "1_1") (pintype "passive"))
      (node (ref "U6") (pin "1") (pinfunction "A_1") (pintype "bidirectional"))
    )
    (net (code "68") (name "Net-(U8-RXLED)") (class "Default")
      (node (ref "RX") (pin "C") (pinfunction "C_C") (pintype "passive"))
      (node (ref "U8") (pin "22") (pinfunction "RXLED_22") (pintype "bidirectional"))
    )
    (net (code "69") (name "Net-(U8-TXLED)") (class "Default")
      (node (ref "TX") (pin "C") (pinfunction "C_C") (pintype "passive"))
      (node (ref "U8") (pin "23") (pinfunction "TXLED_23") (pintype "bidirectional"))
    )
    (net (code "70") (name "Net-(U8-USBDM)") (class "Default")
      (node (ref "JP1") (pin "2") (pinfunction "2_2") (pintype "passive"))
      (node (ref "U8") (pin "16") (pinfunction "USBDM_16") (pintype "bidirectional"))
    )
    (net (code "71") (name "Net-(U8-USBDP)") (class "Default")
      (node (ref "JP1") (pin "1") (pinfunction "1_1") (pintype "passive"))
      (node (ref "U8") (pin "15") (pinfunction "USBDP_15") (pintype "bidirectional"))
    )
    (net (code "72") (name "Net-(U9-~{RST})") (class "Default")
      (node (ref "SJ1") (pin "1") (pinfunction "1_1") (pintype "passive"))
      (node (ref "U9") (pin "1") (pinfunction "~{RST}_1") (pintype "bidirectional"))
    )
    (net (code "73") (name "Net-(U11--IN)") (class "Default")
      (node (ref "R26") (pin "2") (pinfunction "2_2") (pintype "passive"))
      (node (ref "U11") (pin "1") (pinfunction "OUT_1") (pintype "output"))
      (node (ref "U11") (pin "4") (pinfunction "-IN_4") (pintype "input"))
    )
    (net (code "74") (name "Net-(U14-1A)") (class "Default")
      (node (ref "U14") (pin "2") (pinfunction "1A_2") (pintype "bidirectional"))
      (node (ref "U8") (pin "1") (pinfunction "TXD_1") (pintype "output"))
    )
    (net (code "75") (name "Net-(U14-2OE)") (class "Default")
      (node (ref "R38") (pin "1") (pinfunction "1_1") (pintype "passive"))
      (node (ref "U14") (pin "7") (pinfunction "2OE_7") (pintype "bidirectional"))
    )
    (net (code "76") (name "Net-(U14-2Y)") (class "Default")
      (node (ref "U14") (pin "3") (pinfunction "2Y_3") (pintype "bidirectional"))
      (node (ref "U8") (pin "5") (pinfunction "RXD_5") (pintype "input"))
    )
    (net (code "77") (name "unconnected-(CASE2C-5-Pad29)") (class "Default")
      (node (ref "CASE2") (pin "29") (pinfunction "5_29") (pintype "passive"))
    )
    (net (code "78") (name "unconnected-(CASE2C-6-Pad30)") (class "Default")
      (node (ref "CASE2") (pin "30") (pinfunction "6_30") (pintype "passive"))
    )
    (net (code "79") (name "unconnected-(CASE2C-7-Pad31)") (class "Default")
      (node (ref "CASE2") (pin "31") (pinfunction "7_31") (pintype "passive"))
    )
    (net (code "80") (name "unconnected-(CASE2C-8-Pad32)") (class "Default")
      (node (ref "CASE2") (pin "32") (pinfunction "8_32") (pintype "passive"))
    )
    (net (code "81") (name "unconnected-(CASE2C-9-Pad33)") (class "Default")
      (node (ref "CASE2") (pin "33") (pinfunction "9_33") (pintype "passive"))
    )
    (net (code "82") (name "unconnected-(CASE2C-12-Pad36)") (class "Default")
      (node (ref "CASE2") (pin "36") (pinfunction "12_36") (pintype "passive"))
    )
    (net (code "83") (name "unconnected-(CASE2D-8-Pad44)") (class "Default")
      (node (ref "CASE2") (pin "44") (pinfunction "8_44") (pintype "passive"))
    )
    (net (code "84") (name "unconnected-(CASE2D-9-Pad45)") (class "Default")
      (node (ref "CASE2") (pin "45") (pinfunction "9_45") (pintype "passive"))
    )
    (net (code "85") (name "unconnected-(CASE2D-10-Pad46)") (class "Default")
      (node (ref "CASE2") (pin "46") (pinfunction "10_46") (pintype "passive"))
    )
    (net (code "86") (name "unconnected-(CASE2D-11-Pad47)") (class "Default")
      (node (ref "CASE2") (pin "47") (pinfunction "11_47") (pintype "passive"))
    )
    (net (code "87") (name "unconnected-(CASE2D-12-Pad48)") (class "Default")
      (node (ref "CASE2") (pin "48") (pinfunction "12_48") (pintype "passive"))
    )
    (net (code "88") (name "unconnected-(U1-*RP19(1){slash}CN28{slash}PMBE{slash}RC3-Pad36)") (class "Default")
      (node (ref "U1") (pin "36") (pinfunction "*RP19(1)/CN28/PMBE/RC3_36") (pintype "bidirectional"))
    )
    (net (code "89") (name "unconnected-(U1-*TDI{slash}PMA9{slash}RA9-Pad35)") (class "Default")
      (node (ref "U1") (pin "35") (pinfunction "*TDI/PMA9/RA9_35") (pintype "bidirectional"))
    )
    (net (code "90") (name "unconnected-(U1-*TDO{slash}PMA8{slash}RA8-Pad32)") (class "Default")
      (node (ref "U1") (pin "32") (pinfunction "*TDO/PMA8/RA8_32") (pintype "bidirectional"))
    )
    (net (code "91") (name "unconnected-(U1-AN8{slash}CVREF{slash}RP18(1){slash}PMA2{slash}CN10{slash}RC2-Pad27)") (class "Default")
      (node (ref "U1") (pin "27") (pinfunction "AN8/CVREF/RP18(1)/PMA2/CN10/RC2_27") (pintype "bidirectional"))
    )
    (net (code "92") (name "unconnected-(U1-AN9{slash}DAC1LN{slash}RP15(1){slash}CN11{slash}PMCS1{slash}RB15*-Pad15)") (class "Default")
      (node (ref "U1") (pin "15") (pinfunction "AN9/DAC1LN/RP15(1)/CN11/PMCS1/RB15*_15") (pintype "bidirectional"))
    )
    (net (code "93") (name "unconnected-(U1-AN10{slash}DAC1LP{slash}RTCC{slash}RP14*-Pad14)") (class "Default")
      (node (ref "U1") (pin "14") (pinfunction "AN10/DAC1LP/RTCC/RP14*_14") (pintype "bidirectional"))
    )
    (net (code "94") (name "unconnected-(U1-AN11{slash}DAC1RN{slash}RP13(1){slash}CN13{slash}PMRD{slash}RB13-Pad11)") (class "Default")
      (node (ref "U1") (pin "11") (pinfunction "AN11/DAC1RN/RP13(1)/CN13/PMRD/RB13_11") (pintype "bidirectional"))
    )
    (net (code "95") (name "unconnected-(U1-SOSCI{slash}RP4(1){slash}CN1{slash}RB4-Pad33)") (class "Default")
      (node (ref "U1") (pin "33") (pinfunction "SOSCI/RP4(1)/CN1/RB4_33") (pintype "bidirectional"))
    )
    (net (code "96") (name "unconnected-(U1-SOSCO{slash}T1CK{slash}CN0{slash}RA4-Pad34)") (class "Default")
      (node (ref "U1") (pin "34") (pinfunction "SOSCO/T1CK/CN0/RA4_34") (pintype "bidirectional"))
    )
    (net (code "97") (name "unconnected-(U1-TCK{slash}PMA7{slash}RA7*-Pad13)") (class "Default")
      (node (ref "U1") (pin "13") (pinfunction "TCK/PMA7/RA7*_13") (pintype "bidirectional"))
    )
    (net (code "98") (name "unconnected-(U1-TMS{slash}PMA10{slash}RA10*-Pad12)") (class "Default")
      (node (ref "U1") (pin "12") (pinfunction "TMS/PMA10/RA10*_12") (pintype "bidirectional"))
    )
    (net (code "99") (name "unconnected-(U8-CTS-Pad11)") (class "Default")
      (node (ref "U8") (pin "11") (pinfunction "CTS_11") (pintype "bidirectional"))
    )
    (net (code "100") (name "unconnected-(U8-DTR-Pad2)") (class "Default")
      (node (ref "U8") (pin "2") (pinfunction "DTR_2") (pintype "bidirectional"))
    )
    (net (code "101") (name "unconnected-(U8-RTS-Pad3)") (class "Default")
      (node (ref "U8") (pin "3") (pinfunction "RTS_3") (pintype "bidirectional"))
    )
    (net (code "102") (name "unconnected-(U9-~{MR}-Pad3)") (class "Default")
      (node (ref "U9") (pin "3") (pinfunction "~{MR}_3") (pintype "bidirectional"))
    )
  )
)
